# parallelflash.net
KiCad netlist of a schematic drawn in EAGLE
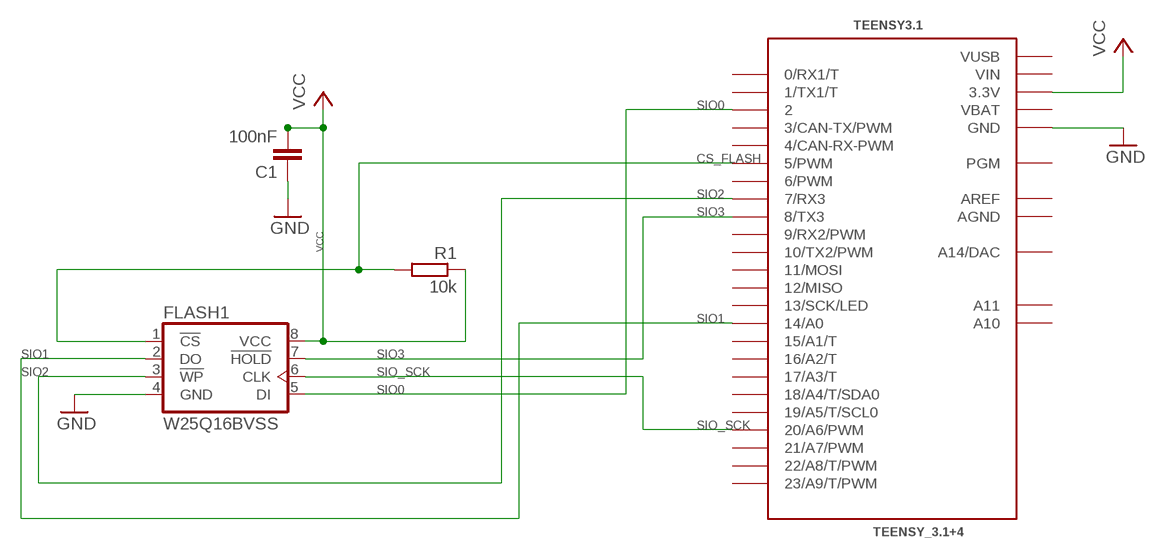
[diagram p0: schematic, sheet 1]

(export (version "E")
  (design (tool "Eeschema 10.0.6"))
  (components
    (comp (ref "C1")
      (value "100nF")
      (footprint "eagle-import:C0603")
      (libsource (lib "eagle-import") (part "C-EUC0603"))
    )
    (comp (ref "FLASH1")
      (value "W25Q16BVSS")
      (footprint "eagle-import:SO08-SS")
      (libsource (lib "eagle-import") (part "W25Q16BVSS"))
    )
    (comp (ref "R1")
      (value "10k")
      (footprint "eagle-import:R0603")
      (libsource (lib "eagle-import") (part "R-EU_R0603"))
    )
    (comp (ref "TEENSY3.1")
      (value "TEENSY_3.1+4")
      (footprint "eagle-import:TEENSY_3.1+4")
      (libsource (lib "eagle-import") (part "TEENSY_3.1+4"))
    )
  )
  (nets
    (net (code "1") (name "/AGND") (class "Default")
      (node (ref "TEENSY3.1") (pin "AGND") (pinfunction "AGND_AGND") (pintype "power_in"))
    )
    (net (code "2") (name "/AREF") (class "Default")
      (node (ref "TEENSY3.1") (pin "AREF") (pinfunction "AREF_AREF") (pintype "power_in"))
    )
    (net (code "3") (name "/CS_FLASH") (class "Default")
      (node (ref "FLASH1") (pin "1") (pinfunction "~{CS}_1") (pintype "input"))
      (node (ref "R1") (pin "2") (pinfunction "2_2") (pintype "passive"))
      (node (ref "TEENSY3.1") (pin "5") (pinfunction "5/PWM_5") (pintype "bidirectional"))
    )
    (net (code "4") (name "/SIO0") (class "Default")
      (node (ref "FLASH1") (pin "5") (pinfunction "DI_5") (pintype "input"))
      (node (ref "TEENSY3.1") (pin "2") (pinfunction "2_2") (pintype "bidirectional"))
    )
    (net (code "5") (name "/SIO1") (class "Default")
      (node (ref "FLASH1") (pin "2") (pinfunction "DO_2") (pintype "output"))
      (node (ref "TEENSY3.1") (pin "14/A0") (pinfunction "14/A0_14/A0") (pintype "bidirectional"))
    )
    (net (code "6") (name "/SIO2") (class "Default")
      (node (ref "FLASH1") (pin "3") (pinfunction "~{WP}_3") (pintype "input"))
      (node (ref "TEENSY3.1") (pin "7") (pinfunction "7/RX3_7") (pintype "bidirectional"))
    )
    (net (code "7") (name "/SIO3") (class "Default")
      (node (ref "FLASH1") (pin "7") (pinfunction "~{HOLD}_7") (pintype "input"))
      (node (ref "TEENSY3.1") (pin "8") (pinfunction "8/TX3_8") (pintype "bidirectional"))
    )
    (net (code "8") (name "/SIO_SCK") (class "Default")
      (node (ref "FLASH1") (pin "6") (pinfunction "CLK_6") (pintype "input"))
      (node (ref "TEENSY3.1") (pin "20/A6") (pinfunction "20/A6/PWM_20/A6") (pintype "bidirectional"))
    )
    (net (code "9") (name "/VBAT") (class "Default")
      (node (ref "TEENSY3.1") (pin "VBAT") (pinfunction "VBAT_VBAT") (pintype "power_in"))
    )
    (net (code "10") (name "/VIN") (class "Default")
      (node (ref "TEENSY3.1") (pin "VIN") (pinfunction "VIN_VIN") (pintype "power_in"))
    )
    (net (code "11") (name "/VUSB") (class "Default")
      (node (ref "TEENSY3.1") (pin "VUSB") (pinfunction "VUSB_VUSB") (pintype "power_in"))
    )
    (net (code "12") (name "GND") (class "Default")
      (node (ref "C1") (pin "1") (pinfunction "1_1") (pintype "passive"))
      (node (ref "FLASH1") (pin "4") (pinfunction "GND_4") (pintype "power_in"))
      (node (ref "TEENSY3.1") (pin "GND") (pinfunction "GND_GND") (pintype "power_in"))
      (node (ref "TEENSY3.1") (pin "GND1") (pinfunction "GND_GND1") (pintype "power_in"))
    )
    (net (code "13") (name "VCC") (class "Default")
      (node (ref "C1") (pin "2") (pinfunction "2_2") (pintype "passive"))
      (node (ref "FLASH1") (pin "8") (pinfunction "VCC_8") (pintype "power_in"))
      (node (ref "R1") (pin "1") (pinfunction "1_1") (pintype "passive"))
      (node (ref "TEENSY3.1") (pin "3.3V") (pinfunction "3.3V_3.3V") (pintype "power_in"))
      (node (ref "TEENSY3.1") (pin "3.3V1") (pinfunction "3.3V_3.3V1") (pintype "power_in"))
    )
    (net (code "14") (name "unconnected-(TEENSY3.1-0{slash}RX1{slash}T-Pad0)") (class "Default")
      (node (ref "TEENSY3.1") (pin "0") (pinfunction "0/RX1/T_0") (pintype "bidirectional"))
    )
    (net (code "15") (name "unconnected-(TEENSY3.1-1{slash}TX1{slash}T-Pad1)") (class "Default")
      (node (ref "TEENSY3.1") (pin "1") (pinfunction "1/TX1/T_1") (pintype "bidirectional"))
    )
    (net (code "16") (name "unconnected-(TEENSY3.1-3{slash}CAN-TX{slash}PWM-Pad3)") (class "Default")
      (node (ref "TEENSY3.1") (pin "3") (pinfunction "3/CAN-TX/PWM_3") (pintype "bidirectional"))
    )
    (net (code "17") (name "unconnected-(TEENSY3.1-4{slash}CAN-RX-PWM-Pad4)") (class "Default")
      (node (ref "TEENSY3.1") (pin "4") (pinfunction "4/CAN-RX-PWM_4") (pintype "bidirectional"))
    )
    (net (code "18") (name "unconnected-(TEENSY3.1-6{slash}PWM-Pad6)") (class "Default")
      (node (ref "TEENSY3.1") (pin "6") (pinfunction "6/PWM_6") (pintype "bidirectional"))
    )
    (net (code "19") (name "unconnected-(TEENSY3.1-9{slash}RX2{slash}PWM-Pad9)") (class "Default")
      (node (ref "TEENSY3.1") (pin "9") (pinfunction "9/RX2/PWM_9") (pintype "bidirectional"))
    )
    (net (code "20") (name "unconnected-(TEENSY3.1-10{slash}TX2{slash}PWM-Pad10)") (class "Default")
      (node (ref "TEENSY3.1") (pin "10") (pinfunction "10/TX2/PWM_10") (pintype "bidirectional"))
    )
    (net (code "21") (name "unconnected-(TEENSY3.1-11{slash}MOSI-Pad11)") (class "Default")
      (node (ref "TEENSY3.1") (pin "11") (pinfunction "11/MOSI_11") (pintype "bidirectional"))
    )
    (net (code "22") (name "unconnected-(TEENSY3.1-12{slash}MISO-Pad12)") (class "Default")
      (node (ref "TEENSY3.1") (pin "12") (pinfunction "12/MISO_12") (pintype "bidirectional"))
    )
    (net (code "23") (name "unconnected-(TEENSY3.1-13{slash}SCK{slash}LED-Pad13)") (class "Default")
      (node (ref "TEENSY3.1") (pin "13") (pinfunction "13/SCK/LED_13") (pintype "bidirectional"))
    )
    (net (code "24") (name "unconnected-(TEENSY3.1-15{slash}A1{slash}T-Pad15{slash}A1)") (class "Default")
      (node (ref "TEENSY3.1") (pin "15/A1") (pinfunction "15/A1/T_15/A1") (pintype "bidirectional"))
    )
    (net (code "25") (name "unconnected-(TEENSY3.1-16{slash}A2{slash}T-Pad16{slash}A2)") (class "Default")
      (node (ref "TEENSY3.1") (pin "16/A2") (pinfunction "16/A2/T_16/A2") (pintype "bidirectional"))
    )
    (net (code "26") (name "unconnected-(TEENSY3.1-17{slash}A3{slash}T-Pad17{slash}A3)") (class "Default")
      (node (ref "TEENSY3.1") (pin "17/A3") (pinfunction "17/A3/T_17/A3") (pintype "bidirectional"))
    )
    (net (code "27") (name "unconnected-(TEENSY3.1-18{slash}A4{slash}T{slash}SDA0-Pad18{slash}A4)") (class "Default")
      (node (ref "TEENSY3.1") (pin "18/A4") (pinfunction "18/A4/T/SDA0_18/A4") (pintype "bidirectional"))
    )
    (net (code "28") (name "unconnected-(TEENSY3.1-19{slash}A5{slash}T{slash}SCL0-Pad19{slash}A5)") (class "Default")
      (node (ref "TEENSY3.1") (pin "19/A5") (pinfunction "19/A5/T/SCL0_19/A5") (pintype "bidirectional"))
    )
    (net (code "29") (name "unconnected-(TEENSY3.1-21{slash}A7{slash}PWM-Pad21{slash}A7)") (class "Default")
      (node (ref "TEENSY3.1") (pin "21/A7") (pinfunction "21/A7/PWM_21/A7") (pintype "bidirectional"))
    )
    (net (code "30") (name "unconnected-(TEENSY3.1-22{slash}A8{slash}T{slash}PWM-Pad22{slash}A8)") (class "Default")
      (node (ref "TEENSY3.1") (pin "22/A8") (pinfunction "22/A8/T/PWM_22/A8") (pintype "bidirectional"))
    )
    (net (code "31") (name "unconnected-(TEENSY3.1-23{slash}A9{slash}T{slash}PWM-Pad23{slash}A9)") (class "Default")
      (node (ref "TEENSY3.1") (pin "23/A9") (pinfunction "23/A9/T/PWM_23/A9") (pintype "bidirectional"))
    )
    (net (code "32") (name "unconnected-(TEENSY3.1-A14{slash}DAC-PadA14)") (class "Default")
      (node (ref "TEENSY3.1") (pin "A14") (pinfunction "A14/DAC_A14") (pintype "bidirectional"))
    )
    (net (code "33") (name "unconnected-(TEENSY3.1-PadA10)") (class "Default")
      (node (ref "TEENSY3.1") (pin "A10") (pinfunction "A10_A10") (pintype "bidirectional"))
    )
    (net (code "34") (name "unconnected-(TEENSY3.1-PadA11)") (class "Default")
      (node (ref "TEENSY3.1") (pin "A11") (pinfunction "A11_A11") (pintype "bidirectional"))
    )
    (net (code "35") (name "unconnected-(TEENSY3.1-PadPGM)") (class "Default")
      (node (ref "TEENSY3.1") (pin "PGM") (pinfunction "PGM_PGM") (pintype "bidirectional"))
    )
  )
)
